# Antenna_Board_v4_2.net
KiCad netlist of a schematic drawn in EAGLE
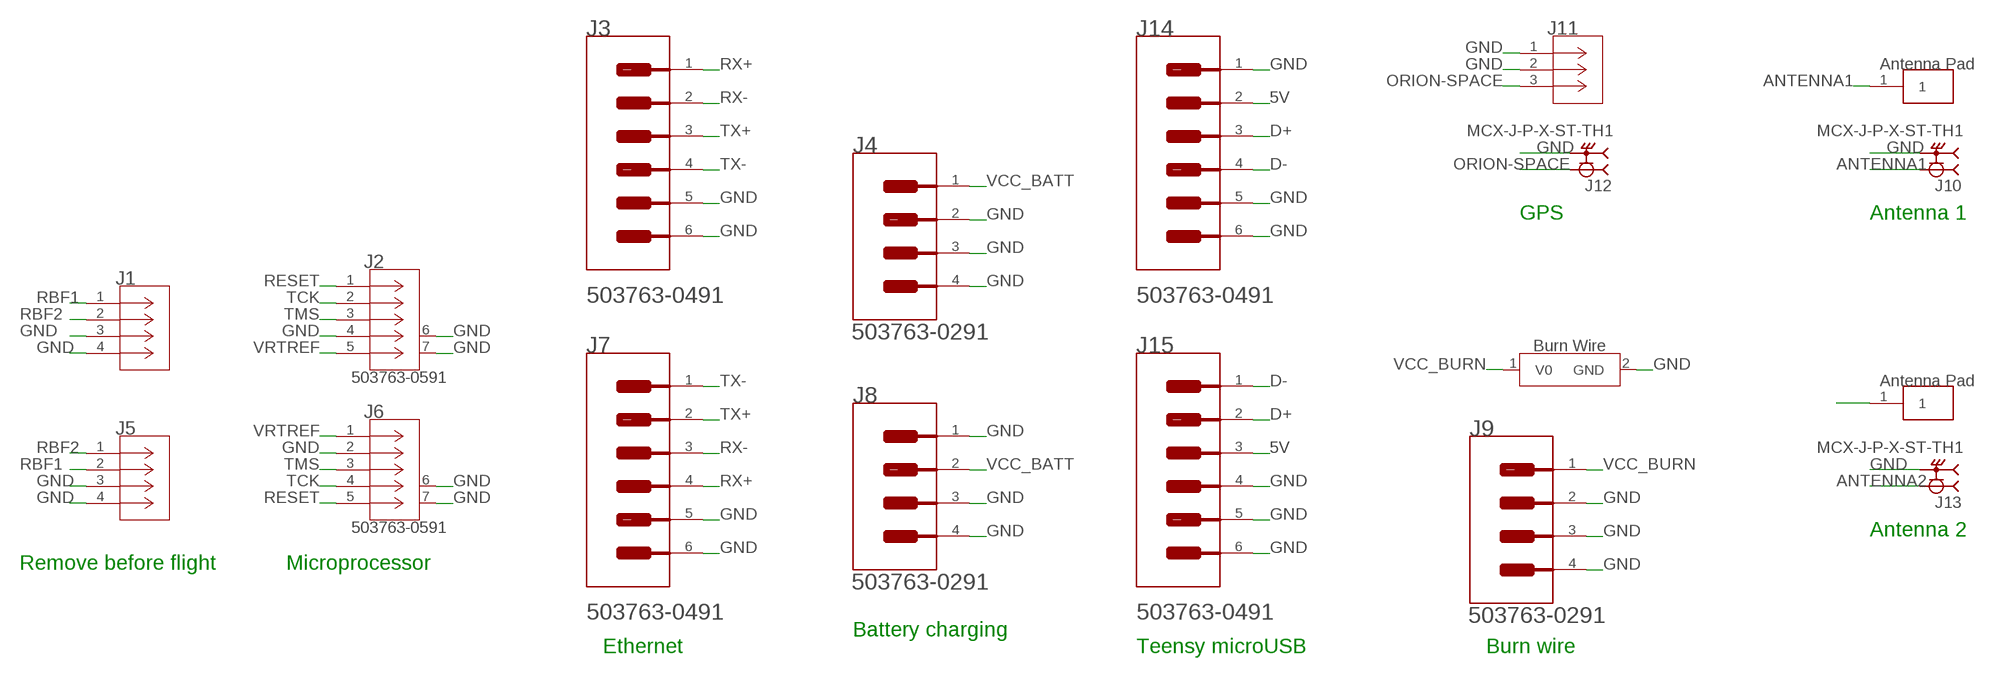
[diagram p0: schematic, sheet 1]

(export (version "E")
  (design (tool "Eeschema 10.0.6"))
  (components
    (comp (ref "J1")
      (value "5037630291")
      (footprint "eagle-import:CON_5037630291")
      (fields (field (name "COPYRIGHT") "Copyright (C) 2018 Accelerated Designs. All rights reserved"))
      (libsource (lib "eagle-import") (part "5037630291"))
    )
    (comp (ref "J2")
      (value "503763-0591")
      (footprint "eagle-import:CONN_5037630591_MOL")
      (fields (field (name "COPYRIGHT") "Copyright (C) 2018 Accelerated Designs. All rights reserved"))
      (libsource (lib "eagle-import") (part "503763-0591"))
    )
    (comp (ref "J3")
      (value "MOLEX_503763-0491MOLEX_503763-0491_0_0")
      (footprint "eagle-import:MOLEX_503763-0491_0")
      (fields
        (field (name "DIGIKEY_PART_NUMBER") "WM10655CT-ND")
        (field (name "MF") "Molex")
        (field (name "MOUSER_PART_NUMBER") "538-503763-0491")
      )
      (libsource (lib "eagle-import") (part "MOLEX_503763-0491MOLEX_503763-0491_0_0"))
    )
    (comp (ref "J4")
      (value "MOLEX_503763-0291MOLEX_503763-0291_0_0")
      (footprint "eagle-import:MOLEX_503763-0291_0")
      (fields
        (field (name "DIGIKEY_PART_NUMBER") "WM10654CT-ND")
        (field (name "MF") "Molex")
        (field (name "MOUSER_PART_NUMBER") "538-503763-0291")
      )
      (libsource (lib "eagle-import") (part "MOLEX_503763-0291MOLEX_503763-0291_0_0"))
    )
    (comp (ref "J5")
      (value "5037630291")
      (footprint "eagle-import:CON_5037630291")
      (fields (field (name "COPYRIGHT") "Copyright (C) 2018 Accelerated Designs. All rights reserved"))
      (libsource (lib "eagle-import") (part "5037630291"))
    )
    (comp (ref "J6")
      (value "503763-0591")
      (footprint "eagle-import:CONN_5037630591_MOL")
      (fields (field (name "COPYRIGHT") "Copyright (C) 2018 Accelerated Designs. All rights reserved"))
      (libsource (lib "eagle-import") (part "503763-0591"))
    )
    (comp (ref "J7")
      (value "MOLEX_503763-0491MOLEX_503763-0491_0_0")
      (footprint "eagle-import:MOLEX_503763-0491_0")
      (fields
        (field (name "DIGIKEY_PART_NUMBER") "WM10655CT-ND")
        (field (name "MF") "Molex")
        (field (name "MOUSER_PART_NUMBER") "538-503763-0491")
      )
      (libsource (lib "eagle-import") (part "MOLEX_503763-0491MOLEX_503763-0491_0_0"))
    )
    (comp (ref "J8")
      (value "MOLEX_503763-0291MOLEX_503763-0291_0_0")
      (footprint "eagle-import:MOLEX_503763-0291_0")
      (fields
        (field (name "DIGIKEY_PART_NUMBER") "WM10654CT-ND")
        (field (name "MF") "Molex")
        (field (name "MOUSER_PART_NUMBER") "538-503763-0291")
      )
      (libsource (lib "eagle-import") (part "MOLEX_503763-0291MOLEX_503763-0291_0_0"))
    )
    (comp (ref "J9")
      (value "MOLEX_503763-0291MOLEX_503763-0291_0_0")
      (footprint "eagle-import:MOLEX_503763-0291_0")
      (fields
        (field (name "DIGIKEY_PART_NUMBER") "WM10654CT-ND")
        (field (name "MF") "Molex")
        (field (name "MOUSER_PART_NUMBER") "538-503763-0291")
      )
      (libsource (lib "eagle-import") (part "MOLEX_503763-0291MOLEX_503763-0291_0_0"))
    )
    (comp (ref "J10")
      (value "MCX-J-P-X-ST-TH1")
      (footprint "eagle-import:SAMTEC_MCX-J-P-X-ST-TH1")
      (fields
        (field (name "DIGI-KEY_PART_NUMBER") "SAM8944-ND")
        (field (name "MF") "Samtec")
        (field (name "MP") "MCX-J-P-H-ST-TH1")
      )
      (libsource (lib "eagle-import") (part "MCX-J-P-X-ST-TH1"))
    )
    (comp (ref "J11")
      (value "U.FL-R-SMT-1(01)")
      (footprint "eagle-import:CONN_-SMT-1(01)")
      (fields (field (name "COPYRIGHT") "Copyright (C) 2018 Accelerated Designs. All rights reserved"))
      (libsource (lib "eagle-import") (part "U.FL-R-SMT-1(01)"))
    )
    (comp (ref "J12")
      (value "MCX-J-P-X-ST-TH1")
      (footprint "eagle-import:SAMTEC_MCX-J-P-X-ST-TH1")
      (fields
        (field (name "DIGI-KEY_PART_NUMBER") "SAM8944-ND")
        (field (name "MF") "Samtec")
        (field (name "MP") "MCX-J-P-H-ST-TH1")
      )
      (libsource (lib "eagle-import") (part "MCX-J-P-X-ST-TH1"))
    )
    (comp (ref "J13")
      (value "MCX-J-P-X-ST-TH1")
      (footprint "eagle-import:SAMTEC_MCX-J-P-X-ST-TH1")
      (fields
        (field (name "DIGI-KEY_PART_NUMBER") "SAM8944-ND")
        (field (name "MF") "Samtec")
        (field (name "MP") "MCX-J-P-H-ST-TH1")
      )
      (libsource (lib "eagle-import") (part "MCX-J-P-X-ST-TH1"))
    )
    (comp (ref "J14")
      (value "MOLEX_503763-0491MOLEX_503763-0491_0_0")
      (footprint "eagle-import:MOLEX_503763-0491_0")
      (fields
        (field (name "DIGIKEY_PART_NUMBER") "WM10655CT-ND")
        (field (name "MF") "Molex")
        (field (name "MOUSER_PART_NUMBER") "538-503763-0491")
      )
      (libsource (lib "eagle-import") (part "MOLEX_503763-0491MOLEX_503763-0491_0_0"))
    )
    (comp (ref "J15")
      (value "MOLEX_503763-0491MOLEX_503763-0491_0_0")
      (footprint "eagle-import:MOLEX_503763-0491_0")
      (fields
        (field (name "DIGIKEY_PART_NUMBER") "WM10655CT-ND")
        (field (name "MF") "Molex")
        (field (name "MOUSER_PART_NUMBER") "538-503763-0491")
      )
      (libsource (lib "eagle-import") (part "MOLEX_503763-0491MOLEX_503763-0491_0_0"))
    )
    (comp (ref "U$1")
      (value "ANTENNA_PAD+HOLES")
      (footprint "eagle-import:ANTENNA_PAD+HOLES")
      (libsource (lib "eagle-import") (part "ANTENNA_PAD+HOLES"))
    )
    (comp (ref "U$2")
      (value "ANTENNA_PAD+HOLES")
      (footprint "eagle-import:ANTENNA_PAD+HOLES")
      (libsource (lib "eagle-import") (part "ANTENNA_PAD+HOLES"))
    )
    (comp (ref "U$3")
      (value "BURNWIRE")
      (footprint "eagle-import:BURNWIRE")
      (libsource (lib "eagle-import") (part "BURNWIRE"))
    )
  )
  (nets
    (net (code "1") (name "/5V") (class "Default")
      (node (ref "J14") (pin "2") (pinfunction "2_2") (pintype "passive"))
      (node (ref "J15") (pin "3") (pinfunction "3_3") (pintype "passive"))
    )
    (net (code "2") (name "/ANTENNA1") (class "Default")
      (node (ref "J10") (pin "1") (pinfunction "1_1") (pintype "passive"))
      (node (ref "U$1") (pin "1") (pinfunction "1_1") (pintype "bidirectional"))
    )
    (net (code "3") (name "/ANTENNA2") (class "Default")
      (node (ref "J13") (pin "1") (pinfunction "1_1") (pintype "passive"))
      (node (ref "U$2") (pin "1") (pinfunction "1_1") (pintype "bidirectional"))
    )
    (net (code "4") (name "/D+") (class "Default")
      (node (ref "J14") (pin "3") (pinfunction "3_3") (pintype "passive"))
      (node (ref "J15") (pin "2") (pinfunction "2_2") (pintype "passive"))
    )
    (net (code "5") (name "/D-") (class "Default")
      (node (ref "J14") (pin "4") (pinfunction "4_4") (pintype "passive"))
      (node (ref "J15") (pin "1") (pinfunction "1_1") (pintype "passive"))
    )
    (net (code "6") (name "/GND") (class "Default")
      (node (ref "J1") (pin "3") (pinfunction "3_3") (pintype "passive"))
      (node (ref "J1") (pin "4") (pinfunction "4_4") (pintype "passive"))
      (node (ref "J10") (pin "S1") (pinfunction "2_S1") (pintype "passive"))
      (node (ref "J10") (pin "S2") (pinfunction "2_S2") (pintype "passive"))
      (node (ref "J10") (pin "S3") (pinfunction "2_S3") (pintype "passive"))
      (node (ref "J10") (pin "S4") (pinfunction "2_S4") (pintype "passive"))
      (node (ref "J11") (pin "1") (pinfunction "1_1") (pintype "passive"))
      (node (ref "J11") (pin "2") (pinfunction "2_2") (pintype "passive"))
      (node (ref "J12") (pin "S1") (pinfunction "2_S1") (pintype "passive"))
      (node (ref "J12") (pin "S2") (pinfunction "2_S2") (pintype "passive"))
      (node (ref "J12") (pin "S3") (pinfunction "2_S3") (pintype "passive"))
      (node (ref "J12") (pin "S4") (pinfunction "2_S4") (pintype "passive"))
      (node (ref "J13") (pin "S1") (pinfunction "2_S1") (pintype "passive"))
      (node (ref "J13") (pin "S2") (pinfunction "2_S2") (pintype "passive"))
      (node (ref "J13") (pin "S3") (pinfunction "2_S3") (pintype "passive"))
      (node (ref "J13") (pin "S4") (pinfunction "2_S4") (pintype "passive"))
      (node (ref "J14") (pin "1") (pinfunction "1_1") (pintype "passive"))
      (node (ref "J14") (pin "5") (pinfunction "MNT_1_5") (pintype "passive"))
      (node (ref "J14") (pin "6") (pinfunction "MNT_2_6") (pintype "passive"))
      (node (ref "J15") (pin "4") (pinfunction "4_4") (pintype "passive"))
      (node (ref "J15") (pin "5") (pinfunction "MNT_1_5") (pintype "passive"))
      (node (ref "J15") (pin "6") (pinfunction "MNT_2_6") (pintype "passive"))
      (node (ref "J2") (pin "4") (pinfunction "4_4") (pintype "passive"))
      (node (ref "J2") (pin "6") (pinfunction "6_6") (pintype "bidirectional"))
      (node (ref "J2") (pin "7") (pinfunction "7_7") (pintype "bidirectional"))
      (node (ref "J3") (pin "5") (pinfunction "MNT_1_5") (pintype "passive"))
      (node (ref "J3") (pin "6") (pinfunction "MNT_2_6") (pintype "passive"))
      (node (ref "J4") (pin "2") (pinfunction "2_2") (pintype "bidirectional"))
      (node (ref "J4") (pin "3") (pinfunction "MNT_1_3") (pintype "bidirectional"))
      (node (ref "J4") (pin "4") (pinfunction "MNT_2_4") (pintype "bidirectional"))
      (node (ref "J5") (pin "3") (pinfunction "3_3") (pintype "passive"))
      (node (ref "J5") (pin "4") (pinfunction "4_4") (pintype "passive"))
      (node (ref "J6") (pin "2") (pinfunction "2_2") (pintype "passive"))
      (node (ref "J6") (pin "6") (pinfunction "6_6") (pintype "bidirectional"))
      (node (ref "J6") (pin "7") (pinfunction "7_7") (pintype "bidirectional"))
      (node (ref "J7") (pin "5") (pinfunction "MNT_1_5") (pintype "passive"))
      (node (ref "J7") (pin "6") (pinfunction "MNT_2_6") (pintype "passive"))
      (node (ref "J8") (pin "1") (pinfunction "1_1") (pintype "bidirectional"))
      (node (ref "J8") (pin "3") (pinfunction "MNT_1_3") (pintype "bidirectional"))
      (node (ref "J8") (pin "4") (pinfunction "MNT_2_4") (pintype "bidirectional"))
      (node (ref "J9") (pin "2") (pinfunction "2_2") (pintype "bidirectional"))
      (node (ref "J9") (pin "3") (pinfunction "MNT_1_3") (pintype "bidirectional"))
      (node (ref "J9") (pin "4") (pinfunction "MNT_2_4") (pintype "bidirectional"))
      (node (ref "U$3") (pin "2") (pinfunction "GND_2") (pintype "bidirectional"))
    )
    (net (code "7") (name "/ORION-SPACE") (class "Default")
      (node (ref "J11") (pin "3") (pinfunction "3_3") (pintype "passive"))
      (node (ref "J12") (pin "1") (pinfunction "1_1") (pintype "passive"))
    )
    (net (code "8") (name "/RBF1") (class "Default")
      (node (ref "J1") (pin "1") (pinfunction "1_1") (pintype "passive"))
      (node (ref "J5") (pin "2") (pinfunction "2_2") (pintype "passive"))
    )
    (net (code "9") (name "/RBF2") (class "Default")
      (node (ref "J1") (pin "2") (pinfunction "2_2") (pintype "passive"))
      (node (ref "J5") (pin "1") (pinfunction "1_1") (pintype "passive"))
    )
    (net (code "10") (name "/RESET") (class "Default")
      (node (ref "J2") (pin "1") (pinfunction "1_1") (pintype "passive"))
      (node (ref "J6") (pin "5") (pinfunction "5_5") (pintype "passive"))
    )
    (net (code "11") (name "/RX+") (class "Default")
      (node (ref "J3") (pin "1") (pinfunction "1_1") (pintype "passive"))
      (node (ref "J7") (pin "4") (pinfunction "4_4") (pintype "passive"))
    )
    (net (code "12") (name "/RX-") (class "Default")
      (node (ref "J3") (pin "2") (pinfunction "2_2") (pintype "passive"))
      (node (ref "J7") (pin "3") (pinfunction "3_3") (pintype "passive"))
    )
    (net (code "13") (name "/TCK") (class "Default")
      (node (ref "J2") (pin "2") (pinfunction "2_2") (pintype "passive"))
      (node (ref "J6") (pin "4") (pinfunction "4_4") (pintype "passive"))
    )
    (net (code "14") (name "/TMS") (class "Default")
      (node (ref "J2") (pin "3") (pinfunction "3_3") (pintype "passive"))
      (node (ref "J6") (pin "3") (pinfunction "3_3") (pintype "passive"))
    )
    (net (code "15") (name "/TX+") (class "Default")
      (node (ref "J3") (pin "3") (pinfunction "3_3") (pintype "passive"))
      (node (ref "J7") (pin "2") (pinfunction "2_2") (pintype "passive"))
    )
    (net (code "16") (name "/TX-") (class "Default")
      (node (ref "J3") (pin "4") (pinfunction "4_4") (pintype "passive"))
      (node (ref "J7") (pin "1") (pinfunction "1_1") (pintype "passive"))
    )
    (net (code "17") (name "/VCC_BATT") (class "Default")
      (node (ref "J4") (pin "1") (pinfunction "1_1") (pintype "bidirectional"))
      (node (ref "J8") (pin "2") (pinfunction "2_2") (pintype "bidirectional"))
    )
    (net (code "18") (name "/VCC_BURN") (class "Default")
      (node (ref "J9") (pin "1") (pinfunction "1_1") (pintype "bidirectional"))
      (node (ref "U$3") (pin "1") (pinfunction "V0_1") (pintype "bidirectional"))
    )
    (net (code "19") (name "/VRTREF") (class "Default")
      (node (ref "J2") (pin "5") (pinfunction "5_5") (pintype "passive"))
      (node (ref "J6") (pin "1") (pinfunction "1_1") (pintype "passive"))
    )
  )
)
